# Prototype_Schematic.net
KiCad netlist of a schematic drawn in EAGLE
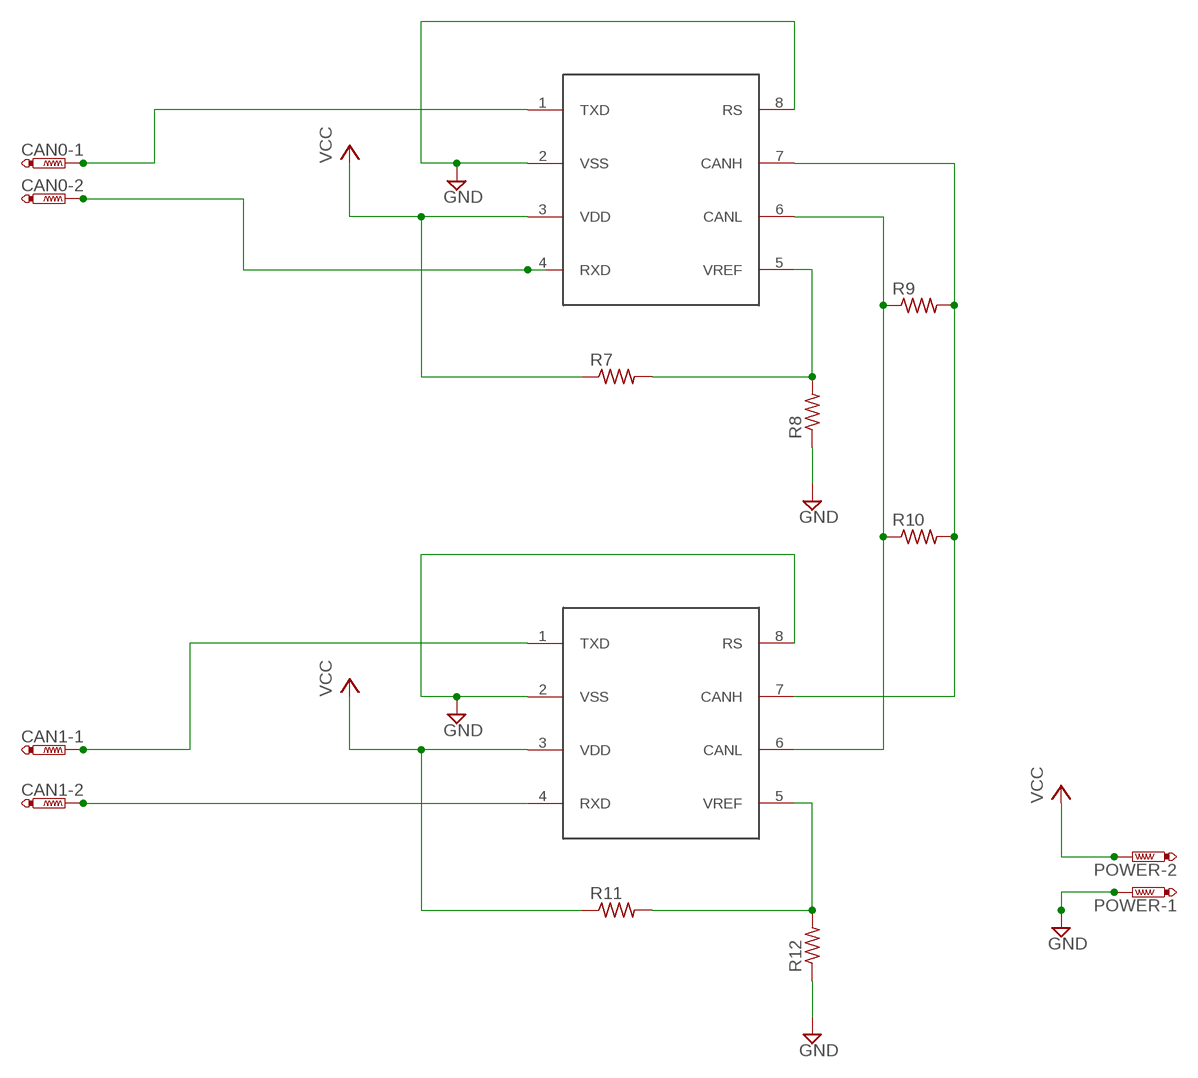
[diagram p0: schematic, sheet 1]

(export (version "E")
  (design (tool "Eeschema 10.0.6"))
  (components
    (comp (ref "CAN0")
      (value "PTR2")
      (footprint "eagle-import:P2-38-17")
      (libsource (lib "eagle-import") (part "PTR2"))
    )
    (comp (ref "CAN1")
      (value "PTR2")
      (footprint "eagle-import:P2-38-17")
      (libsource (lib "eagle-import") (part "PTR2"))
    )
    (comp (ref "POWER")
      (value "PTR2")
      (footprint "eagle-import:P2-38-17")
      (libsource (lib "eagle-import") (part "PTR2"))
    )
    (comp (ref "R7")
      (value "R-US_0204/5")
      (footprint "eagle-import:0204_5")
      (libsource (lib "eagle-import") (part "R-US_0204/5"))
    )
    (comp (ref "R8")
      (value "R-US_0204/5")
      (footprint "eagle-import:0204_5")
      (libsource (lib "eagle-import") (part "R-US_0204/5"))
    )
    (comp (ref "R9")
      (value "R-US_0204/5")
      (footprint "eagle-import:0204_5")
      (libsource (lib "eagle-import") (part "R-US_0204/5"))
    )
    (comp (ref "R10")
      (value "R-US_0204/5")
      (footprint "eagle-import:0204_5")
      (libsource (lib "eagle-import") (part "R-US_0204/5"))
    )
    (comp (ref "R11")
      (value "R-US_0204/5")
      (footprint "eagle-import:0204_5")
      (libsource (lib "eagle-import") (part "R-US_0204/5"))
    )
    (comp (ref "R12")
      (value "R-US_0204/5")
      (footprint "eagle-import:0204_5")
      (libsource (lib "eagle-import") (part "R-US_0204/5"))
    )
    (comp (ref "U$2")
      (value "MCP2551-DIP")
      (footprint "eagle-import:DIL08")
      (libsource (lib "eagle-import") (part "MCP2551-DIP"))
    )
    (comp (ref "U$3")
      (value "MCP2551-DIP")
      (footprint "eagle-import:DIL08")
      (libsource (lib "eagle-import") (part "MCP2551-DIP"))
    )
  )
  (nets
    (net (code "1") (name "GND") (class "Default")
      (node (ref "POWER") (pin "TP-1") (pinfunction "TP_TP-1") (pintype "input"))
      (node (ref "R12") (pin "1") (pinfunction "1_1") (pintype "passive"))
      (node (ref "R8") (pin "1") (pinfunction "1_1") (pintype "passive"))
      (node (ref "U$2") (pin "2") (pinfunction "VSS_2") (pintype "bidirectional"))
      (node (ref "U$2") (pin "8") (pinfunction "RS_8") (pintype "bidirectional"))
      (node (ref "U$3") (pin "2") (pinfunction "VSS_2") (pintype "bidirectional"))
      (node (ref "U$3") (pin "8") (pinfunction "RS_8") (pintype "bidirectional"))
    )
    (net (code "2") (name "Net-(CAN0A-TP)") (class "Default")
      (node (ref "CAN0") (pin "TP-1") (pinfunction "TP_TP-1") (pintype "input"))
      (node (ref "U$2") (pin "1") (pinfunction "TXD_1") (pintype "bidirectional"))
    )
    (net (code "3") (name "Net-(CAN0B-TP)") (class "Default")
      (node (ref "CAN0") (pin "TP-2") (pinfunction "TP_TP-2") (pintype "input"))
      (node (ref "U$2") (pin "4") (pinfunction "RXD_4") (pintype "bidirectional"))
    )
    (net (code "4") (name "Net-(CAN1A-TP)") (class "Default")
      (node (ref "CAN1") (pin "TP-1") (pinfunction "TP_TP-1") (pintype "input"))
      (node (ref "U$3") (pin "1") (pinfunction "TXD_1") (pintype "bidirectional"))
    )
    (net (code "5") (name "Net-(CAN1B-TP)") (class "Default")
      (node (ref "CAN1") (pin "TP-2") (pinfunction "TP_TP-2") (pintype "input"))
      (node (ref "U$3") (pin "4") (pinfunction "RXD_4") (pintype "bidirectional"))
    )
    (net (code "6") (name "Net-(U$2-CANH)") (class "Default")
      (node (ref "R10") (pin "2") (pinfunction "2_2") (pintype "passive"))
      (node (ref "R9") (pin "2") (pinfunction "2_2") (pintype "passive"))
      (node (ref "U$2") (pin "7") (pinfunction "CANH_7") (pintype "bidirectional"))
      (node (ref "U$3") (pin "7") (pinfunction "CANH_7") (pintype "bidirectional"))
    )
    (net (code "7") (name "Net-(U$2-CANL)") (class "Default")
      (node (ref "R10") (pin "1") (pinfunction "1_1") (pintype "passive"))
      (node (ref "R9") (pin "1") (pinfunction "1_1") (pintype "passive"))
      (node (ref "U$2") (pin "6") (pinfunction "CANL_6") (pintype "bidirectional"))
      (node (ref "U$3") (pin "6") (pinfunction "CANL_6") (pintype "bidirectional"))
    )
    (net (code "8") (name "Net-(U$2-VREF)") (class "Default")
      (node (ref "R7") (pin "2") (pinfunction "2_2") (pintype "passive"))
      (node (ref "R8") (pin "2") (pinfunction "2_2") (pintype "passive"))
      (node (ref "U$2") (pin "5") (pinfunction "VREF_5") (pintype "bidirectional"))
    )
    (net (code "9") (name "Net-(U$3-VREF)") (class "Default")
      (node (ref "R11") (pin "2") (pinfunction "2_2") (pintype "passive"))
      (node (ref "R12") (pin "2") (pinfunction "2_2") (pintype "passive"))
      (node (ref "U$3") (pin "5") (pinfunction "VREF_5") (pintype "bidirectional"))
    )
    (net (code "10") (name "VCC") (class "Default")
      (node (ref "POWER") (pin "TP-2") (pinfunction "TP_TP-2") (pintype "input"))
      (node (ref "R11") (pin "1") (pinfunction "1_1") (pintype "passive"))
      (node (ref "R7") (pin "1") (pinfunction "1_1") (pintype "passive"))
      (node (ref "U$2") (pin "3") (pinfunction "VDD_3") (pintype "bidirectional"))
      (node (ref "U$3") (pin "3") (pinfunction "VDD_3") (pintype "bidirectional"))
    )
  )
)
